# GPS_Oszillator.net
KiCad netlist of a schematic drawn in EAGLE
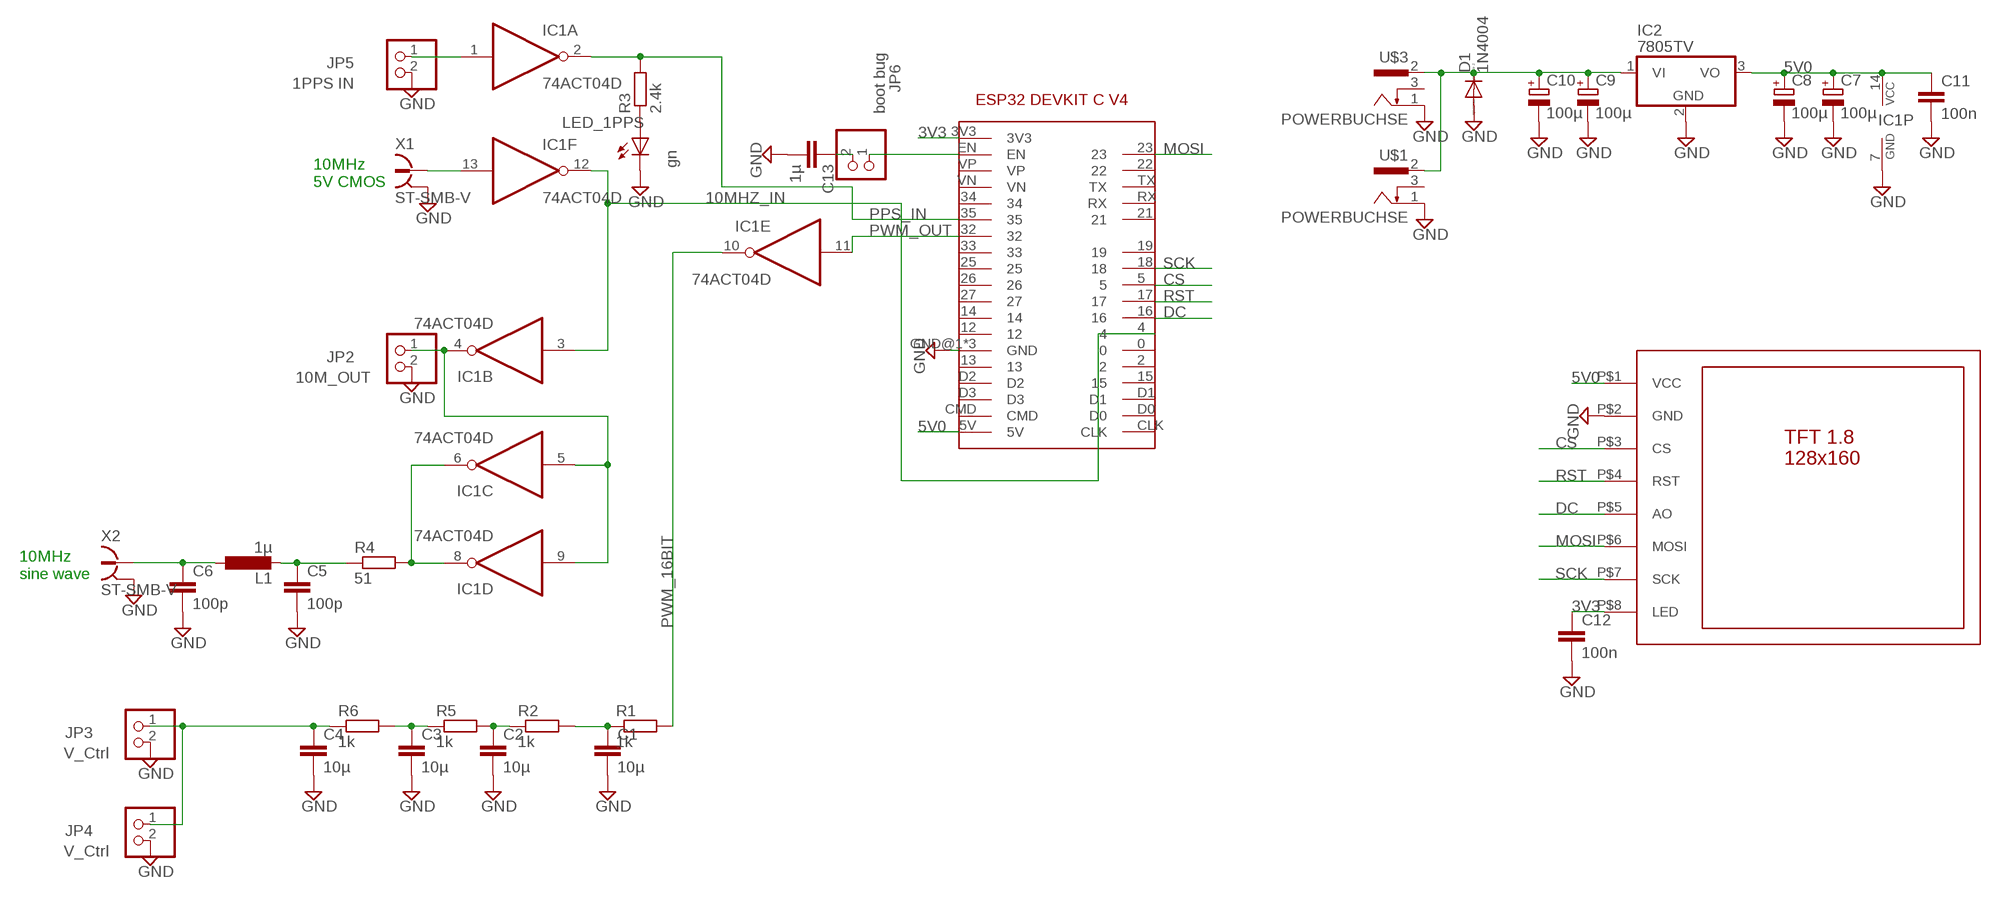
[diagram p0: schematic, sheet 1]

(export (version "E")
  (design (tool "Eeschema 10.0.6"))
  (components
    (comp (ref "C1")
      (value "10µ")
      (footprint "eagle-import:C1206")
      (libsource (lib "eagle-import") (part "C-EUC1206"))
    )
    (comp (ref "C2")
      (value "10µ")
      (footprint "eagle-import:C1206")
      (libsource (lib "eagle-import") (part "C-EUC1206"))
    )
    (comp (ref "C3")
      (value "10µ")
      (footprint "eagle-import:C1206")
      (libsource (lib "eagle-import") (part "C-EUC1206"))
    )
    (comp (ref "C4")
      (value "10µ")
      (footprint "eagle-import:C1206")
      (libsource (lib "eagle-import") (part "C-EUC1206"))
    )
    (comp (ref "C5")
      (value "100p")
      (footprint "eagle-import:C0805")
      (libsource (lib "eagle-import") (part "C-EUC0805"))
    )
    (comp (ref "C6")
      (value "100p")
      (footprint "eagle-import:C0805")
      (libsource (lib "eagle-import") (part "C-EUC0805"))
    )
    (comp (ref "C7")
      (value "100µ")
      (footprint "eagle-import:SANYO-OSCON_SMD_E7")
      (libsource (lib "eagle-import") (part "CPOL-EUSANYO_SMD_E7"))
    )
    (comp (ref "C8")
      (value "100µ")
      (footprint "eagle-import:SANYO-OSCON_SMD_E7")
      (libsource (lib "eagle-import") (part "CPOL-EUSANYO_SMD_E7"))
    )
    (comp (ref "C9")
      (value "100µ")
      (footprint "eagle-import:SANYO-OSCON_SMD_E7")
      (libsource (lib "eagle-import") (part "CPOL-EUSANYO_SMD_E7"))
    )
    (comp (ref "C10")
      (value "100µ")
      (footprint "eagle-import:SANYO-OSCON_SMD_E7")
      (libsource (lib "eagle-import") (part "CPOL-EUSANYO_SMD_E7"))
    )
    (comp (ref "C11")
      (value "100n")
      (footprint "eagle-import:C0805")
      (libsource (lib "eagle-import") (part "C-EUC0805"))
    )
    (comp (ref "C12")
      (value "100n")
      (footprint "eagle-import:C0805")
      (libsource (lib "eagle-import") (part "C-EUC0805"))
    )
    (comp (ref "C13")
      (value "1µ")
      (footprint "eagle-import:C1210")
      (libsource (lib "eagle-import") (part "C-EUC1210"))
    )
    (comp (ref "D1")
      (value "1N4004")
      (footprint "eagle-import:DO41-10")
      (libsource (lib "eagle-import") (part "1N4004"))
    )
    (comp (ref "IC1")
      (value "74ACT04D")
      (footprint "eagle-import:SO14")
      (libsource (lib "eagle-import") (part "7404DACT"))
    )
    (comp (ref "IC2")
      (value "7805TV")
      (footprint "eagle-import:TO220V")
      (libsource (lib "eagle-import") (part "78TV05"))
    )
    (comp (ref "JP2")
      (value "10M_OUT")
      (footprint "eagle-import:1X02")
      (libsource (lib "eagle-import") (part "PINHD-1X2"))
    )
    (comp (ref "JP3")
      (value "V_Ctrl")
      (footprint "eagle-import:1X02")
      (libsource (lib "eagle-import") (part "PINHD-1X2"))
    )
    (comp (ref "JP4")
      (value "V_Ctrl")
      (footprint "eagle-import:1X02")
      (libsource (lib "eagle-import") (part "PINHD-1X2"))
    )
    (comp (ref "JP5")
      (value "1PPS IN")
      (footprint "eagle-import:1X02")
      (libsource (lib "eagle-import") (part "PINHD-1X2"))
    )
    (comp (ref "JP6")
      (value "boot bug")
      (footprint "eagle-import:1X02")
      (libsource (lib "eagle-import") (part "PINHD-1X2"))
    )
    (comp (ref "L1")
      (value "1µ")
      (footprint "eagle-import:L1812")
      (libsource (lib "eagle-import") (part "L-EUL1812"))
    )
    (comp (ref "LED_1PPS")
      (value "gn")
      (footprint "eagle-import:CHIPLED_0805")
      (libsource (lib "eagle-import") (part "LEDCHIPLED_0805"))
    )
    (comp (ref "R1")
      (value "1k")
      (footprint "eagle-import:R0805")
      (libsource (lib "eagle-import") (part "R-EU_R0805"))
    )
    (comp (ref "R2")
      (value "1k")
      (footprint "eagle-import:R0805")
      (libsource (lib "eagle-import") (part "R-EU_R0805"))
    )
    (comp (ref "R3")
      (value "2.4k")
      (footprint "eagle-import:R0805")
      (libsource (lib "eagle-import") (part "R-EU_R0805"))
    )
    (comp (ref "R4")
      (value "51")
      (footprint "eagle-import:R0805")
      (libsource (lib "eagle-import") (part "R-EU_R0805"))
    )
    (comp (ref "R5")
      (value "1k")
      (footprint "eagle-import:R0805")
      (libsource (lib "eagle-import") (part "R-EU_R0805"))
    )
    (comp (ref "R6")
      (value "1k")
      (footprint "eagle-import:R0805")
      (libsource (lib "eagle-import") (part "R-EU_R0805"))
    )
    (comp (ref "U$1")
      (value "POWERBUCHSE")
      (footprint "eagle-import:POWERBUCHSE")
      (libsource (lib "eagle-import") (part "POWERBUCHSE"))
    )
    (comp (ref "U$2")
      (value "TFT_18")
      (footprint "eagle-import:TFT_18")
      (libsource (lib "eagle-import") (part "TFT_18"))
    )
    (comp (ref "U$3")
      (value "POWERBUCHSE")
      (footprint "eagle-import:POWERBUCHSE")
      (libsource (lib "eagle-import") (part "POWERBUCHSE"))
    )
    (comp (ref "U$4")
      (value "ESP32_DEVKITC_V4")
      (footprint "eagle-import:ESP32_DEVKIT_C_V4")
      (libsource (lib "eagle-import") (part "ESP32_DEVKITC_V4"))
    )
    (comp (ref "X1")
      (value "ST-SMB-V")
      (footprint "eagle-import:ST-SMB-V")
      (libsource (lib "eagle-import") (part "ST-SMB-V"))
    )
    (comp (ref "X2")
      (value "ST-SMB-V")
      (footprint "eagle-import:ST-SMB-V")
      (libsource (lib "eagle-import") (part "ST-SMB-V"))
    )
  )
  (nets
    (net (code "1") (name "/3V3") (class "Default")
      (node (ref "C12") (pin "1") (pinfunction "1_1") (pintype "passive"))
      (node (ref "U$2") (pin "P$8") (pinfunction "LED_P$8") (pintype "bidirectional"))
      (node (ref "U$4") (pin "3V3") (pinfunction "3V3_3V3") (pintype "bidirectional"))
    )
    (net (code "2") (name "/5V0") (class "Default")
      (node (ref "C11") (pin "1") (pinfunction "1_1") (pintype "passive"))
      (node (ref "C7") (pin "+") (pinfunction "+_+") (pintype "passive"))
      (node (ref "C8") (pin "+") (pinfunction "+_+") (pintype "passive"))
      (node (ref "IC1") (pin "14") (pinfunction "VCC_14") (pintype "power_in"))
      (node (ref "IC2") (pin "3") (pinfunction "VO_3") (pintype "passive"))
      (node (ref "U$2") (pin "P$1") (pinfunction "VCC_P$1") (pintype "bidirectional"))
      (node (ref "U$4") (pin "5V") (pinfunction "5V_5V") (pintype "bidirectional"))
    )
    (net (code "3") (name "/10MHZ_IN") (class "Default")
      (node (ref "IC1") (pin "12") (pinfunction "O_12") (pintype "output"))
      (node (ref "IC1") (pin "3") (pinfunction "I_3") (pintype "input"))
      (node (ref "U$4") (pin "4") (pinfunction "4_4") (pintype "bidirectional"))
    )
    (net (code "4") (name "/CS") (class "Default")
      (node (ref "U$2") (pin "P$3") (pinfunction "CS_P$3") (pintype "bidirectional"))
      (node (ref "U$4") (pin "5") (pinfunction "5_5") (pintype "bidirectional"))
    )
    (net (code "5") (name "/DC") (class "Default")
      (node (ref "U$2") (pin "P$5") (pinfunction "AO_P$5") (pintype "bidirectional"))
      (node (ref "U$4") (pin "16") (pinfunction "16_16") (pintype "bidirectional"))
    )
    (net (code "6") (name "/MOSI") (class "Default")
      (node (ref "U$2") (pin "P$6") (pinfunction "MOSI_P$6") (pintype "bidirectional"))
      (node (ref "U$4") (pin "23") (pinfunction "23_23") (pintype "bidirectional"))
    )
    (net (code "7") (name "/PPS_IN") (class "Default")
      (node (ref "IC1") (pin "2") (pinfunction "O_2") (pintype "output"))
      (node (ref "R3") (pin "2") (pinfunction "2_2") (pintype "passive"))
      (node (ref "U$4") (pin "35") (pinfunction "35_35") (pintype "bidirectional"))
    )
    (net (code "8") (name "/PWM_16BIT") (class "Default")
      (node (ref "IC1") (pin "10") (pinfunction "O_10") (pintype "output"))
      (node (ref "R1") (pin "2") (pinfunction "2_2") (pintype "passive"))
    )
    (net (code "9") (name "/PWM_OUT") (class "Default")
      (node (ref "IC1") (pin "11") (pinfunction "I_11") (pintype "input"))
      (node (ref "U$4") (pin "32") (pinfunction "32_32") (pintype "bidirectional"))
    )
    (net (code "10") (name "/RST") (class "Default")
      (node (ref "U$2") (pin "P$4") (pinfunction "RST_P$4") (pintype "bidirectional"))
      (node (ref "U$4") (pin "17") (pinfunction "17_17") (pintype "bidirectional"))
    )
    (net (code "11") (name "/SCK") (class "Default")
      (node (ref "U$2") (pin "P$7") (pinfunction "SCK_P$7") (pintype "bidirectional"))
      (node (ref "U$4") (pin "18") (pinfunction "18_18") (pintype "bidirectional"))
    )
    (net (code "12") (name "GND") (class "Default")
      (node (ref "C1") (pin "2") (pinfunction "2_2") (pintype "passive"))
      (node (ref "C10") (pin "-") (pinfunction "-_-") (pintype "passive"))
      (node (ref "C11") (pin "2") (pinfunction "2_2") (pintype "passive"))
      (node (ref "C12") (pin "2") (pinfunction "2_2") (pintype "passive"))
      (node (ref "C13") (pin "2") (pinfunction "2_2") (pintype "passive"))
      (node (ref "C2") (pin "2") (pinfunction "2_2") (pintype "passive"))
      (node (ref "C3") (pin "2") (pinfunction "2_2") (pintype "passive"))
      (node (ref "C4") (pin "2") (pinfunction "2_2") (pintype "passive"))
      (node (ref "C5") (pin "2") (pinfunction "2_2") (pintype "passive"))
      (node (ref "C6") (pin "2") (pinfunction "2_2") (pintype "passive"))
      (node (ref "C7") (pin "-") (pinfunction "-_-") (pintype "passive"))
      (node (ref "C8") (pin "-") (pinfunction "-_-") (pintype "passive"))
      (node (ref "C9") (pin "-") (pinfunction "-_-") (pintype "passive"))
      (node (ref "D1") (pin "A") (pinfunction "A_A") (pintype "passive"))
      (node (ref "IC1") (pin "7") (pinfunction "GND_7") (pintype "power_in"))
      (node (ref "IC2") (pin "2") (pinfunction "GND_2") (pintype "passive"))
      (node (ref "JP2") (pin "2") (pinfunction "2_2") (pintype "passive"))
      (node (ref "JP3") (pin "2") (pinfunction "2_2") (pintype "passive"))
      (node (ref "JP4") (pin "2") (pinfunction "2_2") (pintype "passive"))
      (node (ref "JP5") (pin "2") (pinfunction "2_2") (pintype "passive"))
      (node (ref "LED_1PPS") (pin "C") (pinfunction "C_C") (pintype "passive"))
      (node (ref "U$1") (pin "1") (pinfunction "2_1") (pintype "passive"))
      (node (ref "U$2") (pin "P$2") (pinfunction "GND_P$2") (pintype "bidirectional"))
      (node (ref "U$3") (pin "1") (pinfunction "2_1") (pintype "passive"))
      (node (ref "U$4") (pin "GND@1") (pinfunction "GND_GND@1") (pintype "bidirectional"))
      (node (ref "U$4") (pin "GND@2") (pinfunction "GND_GND@2") (pintype "bidirectional"))
      (node (ref "U$4") (pin "GND@3") (pinfunction "GND_GND@3") (pintype "bidirectional"))
      (node (ref "X1") (pin "2") (pinfunction "2_2") (pintype "passive"))
      (node (ref "X1") (pin "3") (pinfunction "2_3") (pintype "passive"))
      (node (ref "X1") (pin "4") (pinfunction "2_4") (pintype "passive"))
      (node (ref "X1") (pin "5") (pinfunction "2_5") (pintype "passive"))
      (node (ref "X2") (pin "2") (pinfunction "2_2") (pintype "passive"))
      (node (ref "X2") (pin "3") (pinfunction "2_3") (pintype "passive"))
      (node (ref "X2") (pin "4") (pinfunction "2_4") (pintype "passive"))
      (node (ref "X2") (pin "5") (pinfunction "2_5") (pintype "passive"))
    )
    (net (code "13") (name "Net-(C1-Pad1)") (class "Default")
      (node (ref "C1") (pin "1") (pinfunction "1_1") (pintype "passive"))
      (node (ref "R1") (pin "1") (pinfunction "1_1") (pintype "passive"))
      (node (ref "R2") (pin "2") (pinfunction "2_2") (pintype "passive"))
    )
    (net (code "14") (name "Net-(C2-Pad1)") (class "Default")
      (node (ref "C2") (pin "1") (pinfunction "1_1") (pintype "passive"))
      (node (ref "R2") (pin "1") (pinfunction "1_1") (pintype "passive"))
      (node (ref "R5") (pin "2") (pinfunction "2_2") (pintype "passive"))
    )
    (net (code "15") (name "Net-(C3-Pad1)") (class "Default")
      (node (ref "C3") (pin "1") (pinfunction "1_1") (pintype "passive"))
      (node (ref "R5") (pin "1") (pinfunction "1_1") (pintype "passive"))
      (node (ref "R6") (pin "2") (pinfunction "2_2") (pintype "passive"))
    )
    (net (code "16") (name "Net-(C4-Pad1)") (class "Default")
      (node (ref "C4") (pin "1") (pinfunction "1_1") (pintype "passive"))
      (node (ref "JP3") (pin "1") (pinfunction "1_1") (pintype "passive"))
      (node (ref "JP4") (pin "1") (pinfunction "1_1") (pintype "passive"))
      (node (ref "R6") (pin "1") (pinfunction "1_1") (pintype "passive"))
    )
    (net (code "17") (name "Net-(C5-Pad1)") (class "Default")
      (node (ref "C5") (pin "1") (pinfunction "1_1") (pintype "passive"))
      (node (ref "L1") (pin "2") (pinfunction "2_2") (pintype "passive"))
      (node (ref "R4") (pin "1") (pinfunction "1_1") (pintype "passive"))
    )
    (net (code "18") (name "Net-(C6-Pad1)") (class "Default")
      (node (ref "C6") (pin "1") (pinfunction "1_1") (pintype "passive"))
      (node (ref "L1") (pin "1") (pinfunction "1_1") (pintype "passive"))
      (node (ref "X2") (pin "1") (pinfunction "1_1") (pintype "passive"))
    )
    (net (code "19") (name "Net-(C13-Pad1)") (class "Default")
      (node (ref "C13") (pin "1") (pinfunction "1_1") (pintype "passive"))
      (node (ref "JP6") (pin "2") (pinfunction "2_2") (pintype "passive"))
    )
    (net (code "20") (name "Net-(IC1A-I)") (class "Default")
      (node (ref "IC1") (pin "1") (pinfunction "I_1") (pintype "input"))
      (node (ref "JP5") (pin "1") (pinfunction "1_1") (pintype "passive"))
    )
    (net (code "21") (name "Net-(IC1B-O)") (class "Default")
      (node (ref "IC1") (pin "4") (pinfunction "O_4") (pintype "output"))
      (node (ref "IC1") (pin "5") (pinfunction "I_5") (pintype "input"))
      (node (ref "IC1") (pin "9") (pinfunction "I_9") (pintype "input"))
      (node (ref "JP2") (pin "1") (pinfunction "1_1") (pintype "passive"))
    )
    (net (code "22") (name "Net-(IC1C-O)") (class "Default")
      (node (ref "IC1") (pin "6") (pinfunction "O_6") (pintype "output"))
      (node (ref "IC1") (pin "8") (pinfunction "O_8") (pintype "output"))
      (node (ref "R4") (pin "2") (pinfunction "2_2") (pintype "passive"))
    )
    (net (code "23") (name "Net-(IC1F-I)") (class "Default")
      (node (ref "IC1") (pin "13") (pinfunction "I_13") (pintype "input"))
      (node (ref "X1") (pin "1") (pinfunction "1_1") (pintype "passive"))
    )
    (net (code "24") (name "Net-(IC2-VI)") (class "Default")
      (node (ref "C10") (pin "+") (pinfunction "+_+") (pintype "passive"))
      (node (ref "C9") (pin "+") (pinfunction "+_+") (pintype "passive"))
      (node (ref "D1") (pin "C") (pinfunction "C_C") (pintype "passive"))
      (node (ref "IC2") (pin "1") (pinfunction "VI_1") (pintype "input"))
      (node (ref "U$1") (pin "2") (pinfunction "1_2") (pintype "passive"))
      (node (ref "U$3") (pin "2") (pinfunction "1_2") (pintype "passive"))
    )
    (net (code "25") (name "Net-(JP6-Pad1)") (class "Default")
      (node (ref "JP6") (pin "1") (pinfunction "1_1") (pintype "passive"))
      (node (ref "U$4") (pin "EN") (pinfunction "EN_EN") (pintype "bidirectional"))
    )
    (net (code "26") (name "Net-(LED_1PPS-PadA)") (class "Default")
      (node (ref "LED_1PPS") (pin "A") (pinfunction "A_A") (pintype "passive"))
      (node (ref "R3") (pin "1") (pinfunction "1_1") (pintype "passive"))
    )
    (net (code "27") (name "unconnected-(U$1-Pad3)") (class "Default")
      (node (ref "U$1") (pin "3") (pinfunction "3_3") (pintype "passive"))
    )
    (net (code "28") (name "unconnected-(U$3-Pad3)") (class "Default")
      (node (ref "U$3") (pin "3") (pinfunction "3_3") (pintype "passive"))
    )
    (net (code "29") (name "unconnected-(U$4-Pad0)") (class "Default")
      (node (ref "U$4") (pin "0") (pinfunction "0_0") (pintype "bidirectional"))
    )
    (net (code "30") (name "unconnected-(U$4-Pad2)") (class "Default")
      (node (ref "U$4") (pin "2") (pinfunction "2_2") (pintype "bidirectional"))
    )
    (net (code "31") (name "unconnected-(U$4-Pad12)") (class "Default")
      (node (ref "U$4") (pin "12") (pinfunction "12_12") (pintype "bidirectional"))
    )
    (net (code "32") (name "unconnected-(U$4-Pad13)") (class "Default")
      (node (ref "U$4") (pin "13") (pinfunction "13_13") (pintype "bidirectional"))
    )
    (net (code "33") (name "unconnected-(U$4-Pad14)") (class "Default")
      (node (ref "U$4") (pin "14") (pinfunction "14_14") (pintype "bidirectional"))
    )
    (net (code "34") (name "unconnected-(U$4-Pad15)") (class "Default")
      (node (ref "U$4") (pin "15") (pinfunction "15_15") (pintype "bidirectional"))
    )
    (net (code "35") (name "unconnected-(U$4-Pad19)") (class "Default")
      (node (ref "U$4") (pin "19") (pinfunction "19_19") (pintype "bidirectional"))
    )
    (net (code "36") (name "unconnected-(U$4-Pad21)") (class "Default")
      (node (ref "U$4") (pin "21") (pinfunction "21_21") (pintype "bidirectional"))
    )
    (net (code "37") (name "unconnected-(U$4-Pad22)") (class "Default")
      (node (ref "U$4") (pin "22") (pinfunction "22_22") (pintype "bidirectional"))
    )
    (net (code "38") (name "unconnected-(U$4-Pad25)") (class "Default")
      (node (ref "U$4") (pin "25") (pinfunction "25_25") (pintype "bidirectional"))
    )
    (net (code "39") (name "unconnected-(U$4-Pad26)") (class "Default")
      (node (ref "U$4") (pin "26") (pinfunction "26_26") (pintype "bidirectional"))
    )
    (net (code "40") (name "unconnected-(U$4-Pad27)") (class "Default")
      (node (ref "U$4") (pin "27") (pinfunction "27_27") (pintype "bidirectional"))
    )
    (net (code "41") (name "unconnected-(U$4-Pad33)") (class "Default")
      (node (ref "U$4") (pin "33") (pinfunction "33_33") (pintype "bidirectional"))
    )
    (net (code "42") (name "unconnected-(U$4-Pad34)") (class "Default")
      (node (ref "U$4") (pin "34") (pinfunction "34_34") (pintype "bidirectional"))
    )
    (net (code "43") (name "unconnected-(U$4-PadCLK)") (class "Default")
      (node (ref "U$4") (pin "CLK") (pinfunction "CLK_CLK") (pintype "bidirectional"))
    )
    (net (code "44") (name "unconnected-(U$4-PadCMD)") (class "Default")
      (node (ref "U$4") (pin "CMD") (pinfunction "CMD_CMD") (pintype "bidirectional"))
    )
    (net (code "45") (name "unconnected-(U$4-PadD0)") (class "Default")
      (node (ref "U$4") (pin "D0") (pinfunction "D0_D0") (pintype "bidirectional"))
    )
    (net (code "46") (name "unconnected-(U$4-PadD1)") (class "Default")
      (node (ref "U$4") (pin "D1") (pinfunction "D1_D1") (pintype "bidirectional"))
    )
    (net (code "47") (name "unconnected-(U$4-PadD2)") (class "Default")
      (node (ref "U$4") (pin "D2") (pinfunction "D2_D2") (pintype "bidirectional"))
    )
    (net (code "48") (name "unconnected-(U$4-PadD3)") (class "Default")
      (node (ref "U$4") (pin "D3") (pinfunction "D3_D3") (pintype "bidirectional"))
    )
    (net (code "49") (name "unconnected-(U$4-PadRX)") (class "Default")
      (node (ref "U$4") (pin "RX") (pinfunction "RX_RX") (pintype "bidirectional"))
    )
    (net (code "50") (name "unconnected-(U$4-PadTX)") (class "Default")
      (node (ref "U$4") (pin "TX") (pinfunction "TX_TX") (pintype "bidirectional"))
    )
    (net (code "51") (name "unconnected-(U$4-PadVN)") (class "Default")
      (node (ref "U$4") (pin "VN") (pinfunction "VN_VN") (pintype "bidirectional"))
    )
    (net (code "52") (name "unconnected-(U$4-PadVP)") (class "Default")
      (node (ref "U$4") (pin "VP") (pinfunction "VP_VP") (pintype "bidirectional"))
    )
  )
)
